# USB_OTG_FS.net
KiCad netlist of a schematic drawn in Altium Designer
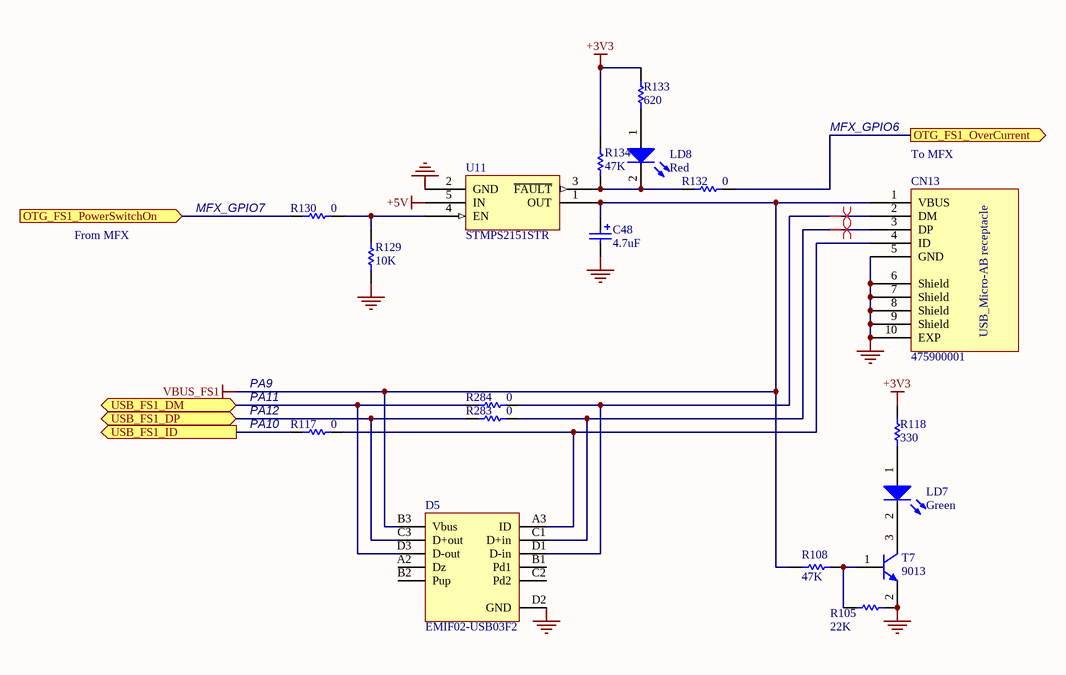
[diagram p0: USB_OTG_FS.SchDoc]

(export (version "E")
  (design (tool "Eeschema 10.0.6"))
  (components
    (comp (ref "C48")
      (value "4.7uF")
      (footprint "TAN-A")
      (description "Polarized Capacitor (Radial)")
      (fields (field (name "PUBLISHER") "Altium Limited"))
      (libsource (lib "Miscellaneous Devices") (part "Cap Pol1"))
    )
    (comp (ref "CN13")
      (value "475900001")
      (footprint "MOLEX_47590001")
      (libsource (lib "mb1045") (part "475900001"))
    )
    (comp (ref "D5")
      (value "EMIF02-USB03F2")
      (footprint "BGA11_0R5_1R57X2R07")
      (libsource (lib "mb1045") (part "EMIF02-USB03F2"))
    )
    (comp (ref "LD7")
      (value "Green")
      (footprint "0603D")
      (description "Typical RED, GREEN, YELLOW, AMBER GaAs LED")
      (fields (field (name "PUBLISHER") "Altium Limited"))
      (libsource (lib "Miscellaneous Devices") (part "LED2"))
    )
    (comp (ref "LD8")
      (value "Red")
      (footprint "0603D")
      (description "Typical RED, GREEN, YELLOW, AMBER GaAs LED")
      (fields (field (name "PUBLISHER") "Altium Limited"))
      (libsource (lib "Miscellaneous Devices") (part "LED2"))
    )
    (comp (ref "R105")
      (value "22K")
      (footprint "0603R")
      (description "Resistor")
      (fields (field (name "PUBLISHER") "Altium Limited"))
      (libsource (lib "Miscellaneous Devices") (part "res1"))
    )
    (comp (ref "R108")
      (value "47K")
      (footprint "0603R")
      (description "Resistor")
      (fields (field (name "PUBLISHER") "Altium Limited"))
      (libsource (lib "Miscellaneous Devices") (part "res1"))
    )
    (comp (ref "R117")
      (value "0")
      (footprint "0603R")
      (description "Resistor")
      (fields (field (name "PUBLISHER") "Altium Limited"))
      (libsource (lib "Miscellaneous Devices") (part "Res1"))
    )
    (comp (ref "R118")
      (value "330")
      (footprint "0603R")
      (description "Resistor")
      (fields (field (name "PUBLISHER") "Altium Limited"))
      (libsource (lib "Miscellaneous Devices") (part "res1"))
    )
    (comp (ref "R129")
      (value "10K")
      (footprint "0603R")
      (description "Resistor")
      (fields (field (name "PUBLISHER") "Altium Limited"))
      (libsource (lib "Miscellaneous Devices") (part "Res1"))
    )
    (comp (ref "R130")
      (value "0")
      (footprint "0603R")
      (description "Resistor")
      (fields (field (name "PUBLISHER") "Altium Limited"))
      (libsource (lib "Miscellaneous Devices") (part "Res1"))
    )
    (comp (ref "R132")
      (value "0")
      (footprint "0603R")
      (description "Resistor")
      (fields (field (name "PUBLISHER") "Altium Limited"))
      (libsource (lib "Miscellaneous Devices") (part "Res1"))
    )
    (comp (ref "R133")
      (value "620")
      (footprint "0603R")
      (description "Resistor")
      (fields (field (name "PUBLISHER") "Altium Limited"))
      (libsource (lib "Miscellaneous Devices") (part "Res1"))
    )
    (comp (ref "R134")
      (value "47K")
      (footprint "0603R")
      (description "Resistor")
      (fields (field (name "PUBLISHER") "Altium Limited"))
      (libsource (lib "Miscellaneous Devices") (part "res1"))
    )
    (comp (ref "R283")
      (value "0")
      (footprint "0603R")
      (description "Resistor")
      (fields (field (name "PUBLISHER") "Altium Limited"))
      (libsource (lib "Miscellaneous Devices") (part "Res1"))
    )
    (comp (ref "R284")
      (value "0")
      (footprint "0603R")
      (description "Resistor")
      (fields (field (name "PUBLISHER") "Altium Limited"))
      (libsource (lib "Miscellaneous Devices") (part "Res1"))
    )
    (comp (ref "T7")
      (value "9013")
      (footprint "SOT-23")
      (description "NPN Bipolar Transistor")
      (fields (field (name "PUBLISHER") "Altium Limited"))
      (libsource (lib "MB1167") (part "NPN"))
    )
    (comp (ref "U11")
      (value "STMPS2151STR")
      (footprint "SOT23-5")
      (libsource (lib "mb1045") (part "STMPS2141STR"))
    )
  )
  (nets
    (net (code "1") (name "+3V3") (class "Default")
      (node (ref "R118") (pin "2") (pinfunction "2_2") (pintype "passive"))
      (node (ref "R133") (pin "2") (pinfunction "2_2") (pintype "passive"))
      (node (ref "R134") (pin "1") (pinfunction "1_1") (pintype "passive"))
    )
    (net (code "2") (name "+5V") (class "Default")
      (node (ref "U11") (pin "5") (pinfunction "IN_5") (pintype "passive"))
    )
    (net (code "3") (name "/OTG_FS1_OverCurrent") (class "Default")
      (node (ref "R132") (pin "1") (pinfunction "1_1") (pintype "passive"))
    )
    (net (code "4") (name "/OTG_FS1_PowerSwitchOn") (class "Default")
      (node (ref "R130") (pin "2") (pinfunction "2_2") (pintype "passive"))
    )
    (net (code "5") (name "/USB_FS1_DM") (class "Default")
      (node (ref "D5") (pin "D3") (pinfunction "D-out_D3") (pintype "passive"))
      (node (ref "R284") (pin "2") (pinfunction "2_2") (pintype "passive"))
    )
    (net (code "6") (name "/USB_FS1_DP") (class "Default")
      (node (ref "D5") (pin "C3") (pinfunction "D+out_C3") (pintype "passive"))
      (node (ref "R283") (pin "2") (pinfunction "2_2") (pintype "passive"))
    )
    (net (code "7") (name "/USB_FS1_ID") (class "Default")
      (node (ref "R117") (pin "2") (pinfunction "2_2") (pintype "passive"))
    )
    (net (code "8") (name "GND") (class "Default")
      (node (ref "C48") (pin "2") (pinfunction "2_2") (pintype "passive"))
      (node (ref "CN13") (pin "10") (pinfunction "EXP_10") (pintype "passive"))
      (node (ref "CN13") (pin "5") (pinfunction "GND_5") (pintype "passive"))
      (node (ref "CN13") (pin "6") (pinfunction "Shield_6") (pintype "passive"))
      (node (ref "CN13") (pin "7") (pinfunction "Shield_7") (pintype "passive"))
      (node (ref "CN13") (pin "8") (pinfunction "Shield_8") (pintype "passive"))
      (node (ref "CN13") (pin "9") (pinfunction "Shield_9") (pintype "passive"))
      (node (ref "D5") (pin "D2") (pinfunction "GND_D2") (pintype "passive"))
      (node (ref "R105") (pin "1") (pinfunction "1_1") (pintype "passive"))
      (node (ref "R129") (pin "1") (pinfunction "1_1") (pintype "passive"))
      (node (ref "T7") (pin "2") (pinfunction "E_2") (pintype "passive"))
      (node (ref "U11") (pin "2") (pinfunction "GND_2") (pintype "passive"))
    )
    (net (code "9") (name "Net-(CN13-DM)") (class "Default")
      (node (ref "CN13") (pin "2") (pinfunction "DM_2") (pintype "passive"))
      (node (ref "D5") (pin "D1") (pinfunction "D-in_D1") (pintype "passive"))
      (node (ref "R284") (pin "1") (pinfunction "1_1") (pintype "passive"))
    )
    (net (code "10") (name "Net-(CN13-DP)") (class "Default")
      (node (ref "CN13") (pin "3") (pinfunction "DP_3") (pintype "passive"))
      (node (ref "D5") (pin "C1") (pinfunction "D+in_C1") (pintype "passive"))
      (node (ref "R283") (pin "1") (pinfunction "1_1") (pintype "passive"))
    )
    (net (code "11") (name "Net-(CN13-ID)") (class "Default")
      (node (ref "CN13") (pin "4") (pinfunction "ID_4") (pintype "passive"))
      (node (ref "D5") (pin "A3") (pinfunction "ID_A3") (pintype "passive"))
      (node (ref "R117") (pin "1") (pinfunction "1_1") (pintype "passive"))
    )
    (net (code "12") (name "Net-(LD7-A)") (class "Default")
      (node (ref "LD7") (pin "1") (pinfunction "A_1") (pintype "passive"))
      (node (ref "R118") (pin "1") (pinfunction "1_1") (pintype "passive"))
    )
    (net (code "13") (name "Net-(LD7-K)") (class "Default")
      (node (ref "LD7") (pin "2") (pinfunction "K_2") (pintype "passive"))
      (node (ref "T7") (pin "3") (pinfunction "C_3") (pintype "passive"))
    )
    (net (code "14") (name "Net-(LD8-A)") (class "Default")
      (node (ref "LD8") (pin "1") (pinfunction "A_1") (pintype "passive"))
      (node (ref "R133") (pin "1") (pinfunction "1_1") (pintype "passive"))
    )
    (net (code "15") (name "Net-(LD8-K)") (class "Default")
      (node (ref "LD8") (pin "2") (pinfunction "K_2") (pintype "passive"))
      (node (ref "R132") (pin "2") (pinfunction "2_2") (pintype "passive"))
      (node (ref "R134") (pin "2") (pinfunction "2_2") (pintype "passive"))
      (node (ref "U11") (pin "3") (pinfunction "~{FAULT}_3") (pintype "output"))
    )
    (net (code "16") (name "Net-(T7-B)") (class "Default")
      (node (ref "R105") (pin "2") (pinfunction "2_2") (pintype "passive"))
      (node (ref "R108") (pin "2") (pinfunction "2_2") (pintype "passive"))
      (node (ref "T7") (pin "1") (pinfunction "B_1") (pintype "passive"))
    )
    (net (code "17") (name "Net-(U11-EN)") (class "Default")
      (node (ref "R129") (pin "2") (pinfunction "2_2") (pintype "passive"))
      (node (ref "R130") (pin "1") (pinfunction "1_1") (pintype "passive"))
      (node (ref "U11") (pin "4") (pinfunction "EN_4") (pintype "input"))
    )
    (net (code "18") (name "VBUS_FS1") (class "Default")
      (node (ref "C48") (pin "1") (pinfunction "1_1") (pintype "passive"))
      (node (ref "CN13") (pin "1") (pinfunction "VBUS_1") (pintype "passive"))
      (node (ref "D5") (pin "B3") (pinfunction "Vbus_B3") (pintype "passive"))
      (node (ref "R108") (pin "1") (pinfunction "1_1") (pintype "passive"))
      (node (ref "U11") (pin "1") (pinfunction "OUT_1") (pintype "passive"))
    )
    (net (code "19") (name "unconnected-(D5-Dz-PadA2)") (class "Default")
      (node (ref "D5") (pin "A2") (pinfunction "Dz_A2") (pintype "passive"))
    )
    (net (code "20") (name "unconnected-(D5-Pd1-PadB1)") (class "Default")
      (node (ref "D5") (pin "B1") (pinfunction "Pd1_B1") (pintype "passive"))
    )
    (net (code "21") (name "unconnected-(D5-Pd2-PadC2)") (class "Default")
      (node (ref "D5") (pin "C2") (pinfunction "Pd2_C2") (pintype "passive"))
    )
    (net (code "22") (name "unconnected-(D5-Pup-PadB2)") (class "Default")
      (node (ref "D5") (pin "B2") (pinfunction "Pup_B2") (pintype "passive"))
    )
  )
)
